# Micro_Rev1j.net
KiCad netlist of a schematic drawn in EAGLE
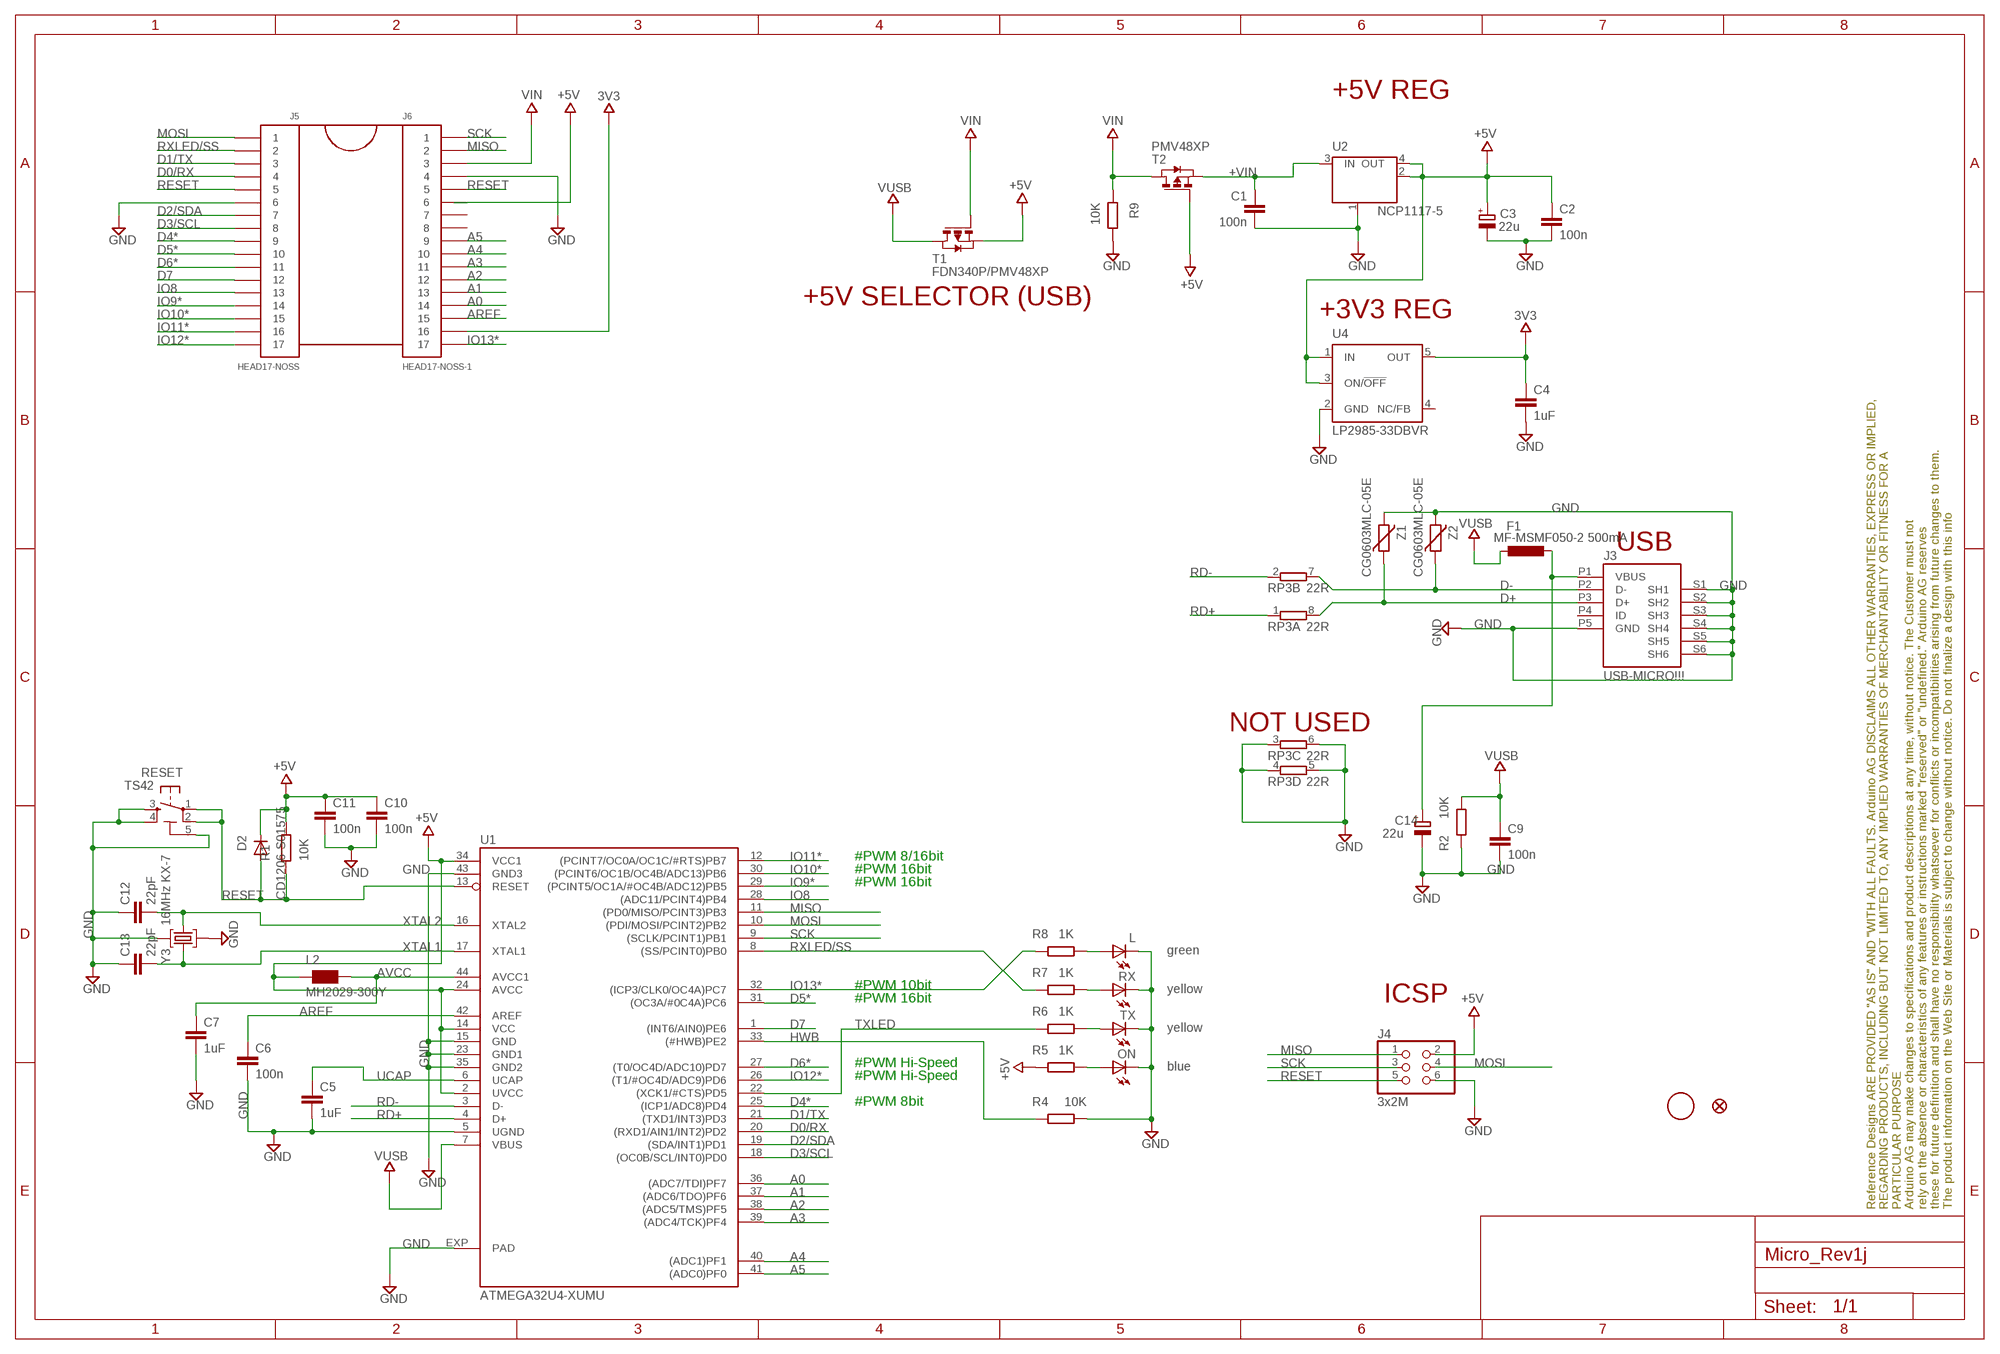
[diagram p0: schematic, sheet 1]

(export (version "E")
  (design (tool "Eeschema 10.0.6"))
  (components
    (comp (ref "C1")
      (value "100n")
      (footprint "eagle-import:C0402")
      (libsource (lib "eagle-import") (part "C-EUC0402"))
    )
    (comp (ref "C2")
      (value "100n")
      (footprint "eagle-import:C0402")
      (libsource (lib "eagle-import") (part "C-EUC0402"))
    )
    (comp (ref "C3")
      (value "22u")
      (footprint "eagle-import:SMC_B")
      (libsource (lib "eagle-import") (part "CPOL-EUSMCB"))
    )
    (comp (ref "C4")
      (value "1uF")
      (footprint "eagle-import:C0402")
      (libsource (lib "eagle-import") (part "C-EUC0402"))
    )
    (comp (ref "C5")
      (value "1uF")
      (footprint "eagle-import:C0402")
      (libsource (lib "eagle-import") (part "C-EUC0402"))
    )
    (comp (ref "C6")
      (value "100n")
      (footprint "eagle-import:C0402")
      (libsource (lib "eagle-import") (part "C-EUC0402"))
    )
    (comp (ref "C7")
      (value "1uF")
      (footprint "eagle-import:C0402")
      (libsource (lib "eagle-import") (part "C-EUC0402"))
    )
    (comp (ref "C9")
      (value "100n")
      (footprint "eagle-import:C0402")
      (libsource (lib "eagle-import") (part "C-EUC0402"))
    )
    (comp (ref "C10")
      (value "100n")
      (footprint "eagle-import:C0402")
      (libsource (lib "eagle-import") (part "C-EUC0402"))
    )
    (comp (ref "C11")
      (value "100n")
      (footprint "eagle-import:C0402")
      (libsource (lib "eagle-import") (part "C-EUC0402"))
    )
    (comp (ref "C12")
      (value "22pF")
      (footprint "eagle-import:C0402")
      (libsource (lib "eagle-import") (part "C-EUC0402"))
    )
    (comp (ref "C13")
      (value "22pF")
      (footprint "eagle-import:C0402")
      (libsource (lib "eagle-import") (part "C-EUC0402"))
    )
    (comp (ref "C14")
      (value "22u")
      (footprint "eagle-import:SMC_B")
      (libsource (lib "eagle-import") (part "CPOL-EUSMCB"))
    )
    (comp (ref "D2")
      (value "CD1206-S01575")
      (footprint "eagle-import:MINIMELF")
      (libsource (lib "eagle-import") (part "DIODE-MINIMELF"))
    )
    (comp (ref "F1")
      (value "MF-MSMF050-2 500mA")
      (footprint "eagle-import:L1812")
      (libsource (lib "eagle-import") (part "L-EUL1812"))
    )
    (comp (ref "FRAME1")
      (value "DNP")
      (footprint "eagle-import:FRAME")
      (libsource (lib "eagle-import") (part "A3-FRAME-STANDARD"))
    )
    (comp (ref "J3")
      (value "USB-MICRO!!!")
      (footprint "eagle-import:CON2_USB_MICRO_B_AT")
      (libsource (lib "eagle-import") (part "MYCON2_USB-MINI-B"))
    )
    (comp (ref "J4")
      (value "3x2M")
      (footprint "eagle-import:2X03")
      (libsource (lib "eagle-import") (part "PINHD-2X3"))
    )
    (comp (ref "J5")
      (value "HEAD17-NOSS")
      (footprint "eagle-import:HEAD17-NOSS")
      (libsource (lib "eagle-import") (part "HEAD17-NOSS"))
    )
    (comp (ref "J6")
      (value "HEAD17-NOSS-1")
      (footprint "eagle-import:HEAD17-NOSS-1")
      (libsource (lib "eagle-import") (part "HEAD17-NOSS-1"))
    )
    (comp (ref "L")
      (value "green")
      (footprint "eagle-import:CHIPLED_0805")
      (libsource (lib "eagle-import") (part "LEDCHIPLED_0805"))
    )
    (comp (ref "L2")
      (value "MH2029-300Y")
      (footprint "eagle-import:0805")
      (libsource (lib "eagle-import") (part "WE-CBF_0805"))
    )
    (comp (ref "ON")
      (value "blue")
      (footprint "eagle-import:CHIPLED_0805")
      (libsource (lib "eagle-import") (part "LEDCHIPLED_0805"))
    )
    (comp (ref "R1")
      (value "10K")
      (footprint "eagle-import:R0402")
      (libsource (lib "eagle-import") (part "R-EU_R0402"))
    )
    (comp (ref "R2")
      (value "10K")
      (footprint "eagle-import:R0402")
      (libsource (lib "eagle-import") (part "R-EU_R0402"))
    )
    (comp (ref "R4")
      (value "10K")
      (footprint "eagle-import:R0402")
      (libsource (lib "eagle-import") (part "R-EU_R0402"))
    )
    (comp (ref "R5")
      (value "1K")
      (footprint "eagle-import:R0402")
      (libsource (lib "eagle-import") (part "R-EU_R0402"))
    )
    (comp (ref "R6")
      (value "1K")
      (footprint "eagle-import:R0402")
      (libsource (lib "eagle-import") (part "R-EU_R0402"))
    )
    (comp (ref "R7")
      (value "1K")
      (footprint "eagle-import:R0402")
      (libsource (lib "eagle-import") (part "R-EU_R0402"))
    )
    (comp (ref "R8")
      (value "1K")
      (footprint "eagle-import:R0402")
      (libsource (lib "eagle-import") (part "R-EU_R0402"))
    )
    (comp (ref "R9")
      (value "10K")
      (footprint "eagle-import:R0402")
      (libsource (lib "eagle-import") (part "R-EU_R0402"))
    )
    (comp (ref "RESET")
      (value "TS42")
      (footprint "eagle-import:TS42")
      (libsource (lib "eagle-import") (part "TS42"))
    )
    (comp (ref "RP3")
      (value "22R")
      (footprint "eagle-import:CAY16")
      (libsource (lib "eagle-import") (part "4R-NCAY16"))
    )
    (comp (ref "RX")
      (value "yellow")
      (footprint "eagle-import:CHIPLED_0805")
      (libsource (lib "eagle-import") (part "LEDCHIPLED_0805"))
    )
    (comp (ref "T1")
      (value "FDN340P/PMV48XP")
      (footprint "eagle-import:SOT-23")
      (libsource (lib "eagle-import") (part "PMOSSOT23"))
    )
    (comp (ref "T2")
      (value "PMV48XP")
      (footprint "eagle-import:SOT-23")
      (libsource (lib "eagle-import") (part "PMOSSOT23"))
    )
    (comp (ref "TX")
      (value "yellow")
      (footprint "eagle-import:CHIPLED_0805")
      (libsource (lib "eagle-import") (part "LEDCHIPLED_0805"))
    )
    (comp (ref "U$37")
      (value "FIDUCIALMOUNT")
      (footprint "eagle-import:FIDUCIA-MOUNT")
      (libsource (lib "eagle-import") (part "FIDUCIALMOUNT"))
    )
    (comp (ref "U$53")
      (value "FIDUCIAL1X2")
      (footprint "eagle-import:FIDUCIAL-1X2")
      (libsource (lib "eagle-import") (part "FIDUCIAL1X2"))
    )
    (comp (ref "U1")
      (value "ATMEGA32U4-XUMU")
      (footprint "eagle-import:QFN44ML7X7")
      (libsource (lib "eagle-import") (part "ATMEGA32U4-XUMU"))
    )
    (comp (ref "U2")
      (value "NCP1117-5")
      (footprint "eagle-import:SOT223")
      (libsource (lib "eagle-import") (part "LINEAR_MC33269ST"))
    )
    (comp (ref "U4")
      (value "LP2985-33DBVR")
      (footprint "eagle-import:SOT23-DBV")
      (libsource (lib "eagle-import") (part "LP2985-XXDBVR33"))
    )
    (comp (ref "Y3")
      (value "16MHz KX-7")
      (footprint "eagle-import:CRYSTAL-3.2-2.5")
      (libsource (lib "eagle-import") (part "CRYSTAL-3.2-2.5"))
    )
    (comp (ref "Z1")
      (value "CG0603MLC-05E")
      (footprint "eagle-import:CT_CN0603")
      (libsource (lib "eagle-import") (part "VARISTORCN0603"))
    )
    (comp (ref "Z2")
      (value "CG0603MLC-05E")
      (footprint "eagle-import:CT_CN0603")
      (libsource (lib "eagle-import") (part "VARISTORCN0603"))
    )
  )
  (nets
    (net (code "1") (name "+5V") (class "Default")
      (node (ref "C10") (pin "1") (pinfunction "1_1") (pintype "passive"))
      (node (ref "C11") (pin "1") (pinfunction "1_1") (pintype "passive"))
      (node (ref "C2") (pin "1") (pinfunction "1_1") (pintype "passive"))
      (node (ref "C3") (pin "+") (pinfunction "+_+") (pintype "passive"))
      (node (ref "D2") (pin "C") (pinfunction "C_C") (pintype "passive"))
      (node (ref "J4") (pin "2") (pinfunction "2_2") (pintype "passive"))
      (node (ref "J6") (pin "6") (pinfunction "6_6") (pintype "passive"))
      (node (ref "L2") (pin "1") (pinfunction "1_1") (pintype "passive"))
      (node (ref "R1") (pin "1") (pinfunction "1_1") (pintype "passive"))
      (node (ref "R5") (pin "1") (pinfunction "1_1") (pintype "passive"))
      (node (ref "T1") (pin "2") (pinfunction "S_2") (pintype "passive"))
      (node (ref "T2") (pin "3") (pinfunction "G_3") (pintype "passive"))
      (node (ref "U1") (pin "14") (pinfunction "VCC_14") (pintype "power_in"))
      (node (ref "U1") (pin "2") (pinfunction "UVCC_2") (pintype "power_in"))
      (node (ref "U1") (pin "24") (pinfunction "AVCC_24") (pintype "power_in"))
      (node (ref "U1") (pin "34") (pinfunction "VCC1_34") (pintype "power_in"))
      (node (ref "U2") (pin "2") (pinfunction "OUT_2") (pintype "passive"))
      (node (ref "U2") (pin "4") (pinfunction "OUT_4") (pintype "passive"))
      (node (ref "U4") (pin "1") (pinfunction "IN_1") (pintype "input"))
      (node (ref "U4") (pin "3") (pinfunction "ON/~{OFF}_3") (pintype "input"))
    )
    (net (code "2") (name "/+VIN") (class "Default")
      (node (ref "C1") (pin "1") (pinfunction "1_1") (pintype "passive"))
      (node (ref "T2") (pin "2") (pinfunction "S_2") (pintype "passive"))
      (node (ref "U2") (pin "3") (pinfunction "IN_3") (pintype "input"))
    )
    (net (code "3") (name "/A0") (class "Default")
      (node (ref "J6") (pin "14") (pinfunction "14_14") (pintype "passive"))
      (node (ref "U1") (pin "36") (pinfunction "(ADC7/TDI)PF7_36") (pintype "bidirectional"))
    )
    (net (code "4") (name "/A1") (class "Default")
      (node (ref "J6") (pin "13") (pinfunction "13_13") (pintype "passive"))
      (node (ref "U1") (pin "37") (pinfunction "(ADC6/TDO)PF6_37") (pintype "bidirectional"))
    )
    (net (code "5") (name "/A2") (class "Default")
      (node (ref "J6") (pin "12") (pinfunction "12_12") (pintype "passive"))
      (node (ref "U1") (pin "38") (pinfunction "(ADC5/TMS)PF5_38") (pintype "bidirectional"))
    )
    (net (code "6") (name "/A3") (class "Default")
      (node (ref "J6") (pin "11") (pinfunction "11_11") (pintype "passive"))
      (node (ref "U1") (pin "39") (pinfunction "(ADC4/TCK)PF4_39") (pintype "bidirectional"))
    )
    (net (code "7") (name "/A4") (class "Default")
      (node (ref "J6") (pin "10") (pinfunction "10_10") (pintype "passive"))
      (node (ref "U1") (pin "40") (pinfunction "(ADC1)PF1_40") (pintype "bidirectional"))
    )
    (net (code "8") (name "/A5") (class "Default")
      (node (ref "J6") (pin "9") (pinfunction "9_9") (pintype "passive"))
      (node (ref "U1") (pin "41") (pinfunction "(ADC0)PF0_41") (pintype "bidirectional"))
    )
    (net (code "9") (name "/AREF") (class "Default")
      (node (ref "C6") (pin "1") (pinfunction "1_1") (pintype "passive"))
      (node (ref "J6") (pin "15") (pinfunction "15_15") (pintype "passive"))
      (node (ref "U1") (pin "42") (pinfunction "AREF_42") (pintype "power_in"))
    )
    (net (code "10") (name "/AVCC") (class "Default")
      (node (ref "C7") (pin "1") (pinfunction "1_1") (pintype "passive"))
      (node (ref "L2") (pin "2") (pinfunction "2_2") (pintype "passive"))
      (node (ref "U1") (pin "44") (pinfunction "AVCC1_44") (pintype "power_in"))
    )
    (net (code "11") (name "/D+") (class "Default")
      (node (ref "J3") (pin "P3") (pinfunction "D+_P3") (pintype "bidirectional"))
      (node (ref "RP3") (pin "8") (pinfunction "2_8") (pintype "passive"))
      (node (ref "Z1") (pin "1") (pinfunction "1_1") (pintype "passive"))
    )
    (net (code "12") (name "/D-") (class "Default")
      (node (ref "J3") (pin "P2") (pinfunction "D-_P2") (pintype "bidirectional"))
      (node (ref "RP3") (pin "7") (pinfunction "2_7") (pintype "passive"))
      (node (ref "Z2") (pin "1") (pinfunction "1_1") (pintype "passive"))
    )
    (net (code "13") (name "/D0{slash}RX") (class "Default")
      (node (ref "J5") (pin "4") (pinfunction "4_4") (pintype "passive"))
      (node (ref "U1") (pin "20") (pinfunction "(RXD1/AIN1/INT2)PD2_20") (pintype "bidirectional"))
    )
    (net (code "14") (name "/D1{slash}TX") (class "Default")
      (node (ref "J5") (pin "3") (pinfunction "3_3") (pintype "passive"))
      (node (ref "U1") (pin "21") (pinfunction "(TXD1/INT3)PD3_21") (pintype "bidirectional"))
    )
    (net (code "15") (name "/D2{slash}SDA") (class "Default")
      (node (ref "J5") (pin "7") (pinfunction "7_7") (pintype "passive"))
      (node (ref "U1") (pin "19") (pinfunction "(SDA/INT1)PD1_19") (pintype "bidirectional"))
    )
    (net (code "16") (name "/D3{slash}SCL") (class "Default")
      (node (ref "J5") (pin "8") (pinfunction "8_8") (pintype "passive"))
      (node (ref "U1") (pin "18") (pinfunction "(OC0B/SCL/INT0)PD0_18") (pintype "bidirectional"))
    )
    (net (code "17") (name "/D4*") (class "Default")
      (node (ref "J5") (pin "9") (pinfunction "9_9") (pintype "passive"))
      (node (ref "U1") (pin "25") (pinfunction "(ICP1/ADC8)PD4_25") (pintype "bidirectional"))
    )
    (net (code "18") (name "/D5*") (class "Default")
      (node (ref "J5") (pin "10") (pinfunction "10_10") (pintype "passive"))
      (node (ref "U1") (pin "31") (pinfunction "(OC3A/#0C4A)PC6_31") (pintype "bidirectional"))
    )
    (net (code "19") (name "/D6*") (class "Default")
      (node (ref "J5") (pin "11") (pinfunction "11_11") (pintype "passive"))
      (node (ref "U1") (pin "27") (pinfunction "(T0/OC4D/ADC10)PD7_27") (pintype "bidirectional"))
    )
    (net (code "20") (name "/D7") (class "Default")
      (node (ref "J5") (pin "12") (pinfunction "12_12") (pintype "passive"))
      (node (ref "U1") (pin "1") (pinfunction "(INT6/AIN0)PE6_1") (pintype "bidirectional"))
    )
    (net (code "21") (name "/HWB") (class "Default")
      (node (ref "R4") (pin "1") (pinfunction "1_1") (pintype "passive"))
      (node (ref "U1") (pin "33") (pinfunction "(#HWB)PE2_33") (pintype "bidirectional"))
    )
    (net (code "22") (name "/IO8") (class "Default")
      (node (ref "J5") (pin "13") (pinfunction "13_13") (pintype "passive"))
      (node (ref "U1") (pin "28") (pinfunction "(ADC11/PCINT4)PB4_28") (pintype "bidirectional"))
    )
    (net (code "23") (name "/IO9*") (class "Default")
      (node (ref "J5") (pin "14") (pinfunction "14_14") (pintype "passive"))
      (node (ref "U1") (pin "29") (pinfunction "(PCINT5/OC1A/#OC4B/ADC12)PB5_29") (pintype "bidirectional"))
    )
    (net (code "24") (name "/IO10*") (class "Default")
      (node (ref "J5") (pin "15") (pinfunction "15_15") (pintype "passive"))
      (node (ref "U1") (pin "30") (pinfunction "(PCINT6/OC1B/OC4B/ADC13)PB6_30") (pintype "bidirectional"))
    )
    (net (code "25") (name "/IO11*") (class "Default")
      (node (ref "J5") (pin "16") (pinfunction "16_16") (pintype "passive"))
      (node (ref "U1") (pin "12") (pinfunction "(PCINT7/OC0A/OC1C/#RTS)PB7_12") (pintype "bidirectional"))
    )
    (net (code "26") (name "/IO12*") (class "Default")
      (node (ref "J5") (pin "17") (pinfunction "17_17") (pintype "passive"))
      (node (ref "U1") (pin "26") (pinfunction "(T1/#OC4D/ADC9)PD6_26") (pintype "bidirectional"))
    )
    (net (code "27") (name "/IO13*") (class "Default")
      (node (ref "J6") (pin "17") (pinfunction "17_17") (pintype "passive"))
      (node (ref "R8") (pin "1") (pinfunction "1_1") (pintype "passive"))
      (node (ref "U1") (pin "32") (pinfunction "(ICP3/CLK0/OC4A)PC7_32") (pintype "bidirectional"))
    )
    (net (code "28") (name "/MISO") (class "Default")
      (node (ref "J4") (pin "1") (pinfunction "1_1") (pintype "passive"))
      (node (ref "J6") (pin "2") (pinfunction "2_2") (pintype "passive"))
      (node (ref "U1") (pin "11") (pinfunction "(PD0/MISO/PCINT3)PB3_11") (pintype "bidirectional"))
    )
    (net (code "29") (name "/MOSI") (class "Default")
      (node (ref "J4") (pin "4") (pinfunction "4_4") (pintype "passive"))
      (node (ref "J5") (pin "1") (pinfunction "1_1") (pintype "passive"))
      (node (ref "U1") (pin "10") (pinfunction "(PDI/MOSI/PCINT2)PB2_10") (pintype "bidirectional"))
    )
    (net (code "30") (name "/RD+") (class "Default")
      (node (ref "RP3") (pin "1") (pinfunction "1_1") (pintype "passive"))
      (node (ref "U1") (pin "4") (pinfunction "D+_4") (pintype "bidirectional"))
    )
    (net (code "31") (name "/RD-") (class "Default")
      (node (ref "RP3") (pin "2") (pinfunction "1_2") (pintype "passive"))
      (node (ref "U1") (pin "3") (pinfunction "D-_3") (pintype "bidirectional"))
    )
    (net (code "32") (name "/RESET") (class "Default")
      (node (ref "D2") (pin "A") (pinfunction "A_A") (pintype "passive"))
      (node (ref "J4") (pin "5") (pinfunction "5_5") (pintype "passive"))
      (node (ref "J5") (pin "5") (pinfunction "5_5") (pintype "passive"))
      (node (ref "J6") (pin "5") (pinfunction "5_5") (pintype "passive"))
      (node (ref "R1") (pin "2") (pinfunction "2_2") (pintype "passive"))
      (node (ref "RESET") (pin "1") (pinfunction "1_1") (pintype "passive"))
      (node (ref "RESET") (pin "2") (pinfunction "2_2") (pintype "passive"))
      (node (ref "U1") (pin "13") (pinfunction "RESET_13") (pintype "input"))
    )
    (net (code "33") (name "/RXLED{slash}SS") (class "Default")
      (node (ref "J5") (pin "2") (pinfunction "2_2") (pintype "passive"))
      (node (ref "R7") (pin "1") (pinfunction "1_1") (pintype "passive"))
      (node (ref "U1") (pin "8") (pinfunction "(SS/PCINT0)PB0_8") (pintype "bidirectional"))
    )
    (net (code "34") (name "/SCK") (class "Default")
      (node (ref "J4") (pin "3") (pinfunction "3_3") (pintype "passive"))
      (node (ref "J6") (pin "1") (pinfunction "1_1") (pintype "passive"))
      (node (ref "U1") (pin "9") (pinfunction "(SCLK/PCINT1)PB1_9") (pintype "bidirectional"))
    )
    (net (code "35") (name "/TXLED") (class "Default")
      (node (ref "R6") (pin "1") (pinfunction "1_1") (pintype "passive"))
      (node (ref "U1") (pin "22") (pinfunction "(XCK1/#CTS)PD5_22") (pintype "bidirectional"))
    )
    (net (code "36") (name "/UCAP") (class "Default")
      (node (ref "C5") (pin "1") (pinfunction "1_1") (pintype "passive"))
      (node (ref "U1") (pin "6") (pinfunction "UCAP_6") (pintype "passive"))
    )
    (net (code "37") (name "/XTAL1") (class "Default")
      (node (ref "C13") (pin "2") (pinfunction "2_2") (pintype "passive"))
      (node (ref "U1") (pin "17") (pinfunction "XTAL1_17") (pintype "bidirectional"))
      (node (ref "Y3") (pin "3") (pinfunction "C2_3") (pintype "passive"))
    )
    (net (code "38") (name "/XTAL2") (class "Default")
      (node (ref "C12") (pin "2") (pinfunction "2_2") (pintype "passive"))
      (node (ref "U1") (pin "16") (pinfunction "XTAL2_16") (pintype "bidirectional"))
      (node (ref "Y3") (pin "1") (pinfunction "C1_1") (pintype "passive"))
    )
    (net (code "39") (name "3V3") (class "Default")
      (node (ref "C4") (pin "1") (pinfunction "1_1") (pintype "passive"))
      (node (ref "J6") (pin "16") (pinfunction "16_16") (pintype "passive"))
      (node (ref "U4") (pin "5") (pinfunction "OUT_5") (pintype "passive"))
    )
    (net (code "40") (name "GND") (class "Default")
      (node (ref "C1") (pin "2") (pinfunction "2_2") (pintype "passive"))
      (node (ref "C10") (pin "2") (pinfunction "2_2") (pintype "passive"))
      (node (ref "C11") (pin "2") (pinfunction "2_2") (pintype "passive"))
      (node (ref "C12") (pin "1") (pinfunction "1_1") (pintype "passive"))
      (node (ref "C13") (pin "1") (pinfunction "1_1") (pintype "passive"))
      (node (ref "C14") (pin "-") (pinfunction "-_-") (pintype "passive"))
      (node (ref "C2") (pin "2") (pinfunction "2_2") (pintype "passive"))
      (node (ref "C3") (pin "-") (pinfunction "-_-") (pintype "passive"))
      (node (ref "C4") (pin "2") (pinfunction "2_2") (pintype "passive"))
      (node (ref "C5") (pin "2") (pinfunction "2_2") (pintype "passive"))
      (node (ref "C6") (pin "2") (pinfunction "2_2") (pintype "passive"))
      (node (ref "C7") (pin "2") (pinfunction "2_2") (pintype "passive"))
      (node (ref "C9") (pin "2") (pinfunction "2_2") (pintype "passive"))
      (node (ref "J3") (pin "P5") (pinfunction "GND_P5") (pintype "passive"))
      (node (ref "J3") (pin "S1") (pinfunction "SH1_S1") (pintype "passive"))
      (node (ref "J3") (pin "S2") (pinfunction "SH2_S2") (pintype "passive"))
      (node (ref "J3") (pin "S3") (pinfunction "SH3_S3") (pintype "passive"))
      (node (ref "J3") (pin "S4") (pinfunction "SH4_S4") (pintype "passive"))
      (node (ref "J3") (pin "S5") (pinfunction "SH5_S5") (pintype "passive"))
      (node (ref "J3") (pin "S6") (pinfunction "SH6_S6") (pintype "passive"))
      (node (ref "J4") (pin "6") (pinfunction "6_6") (pintype "passive"))
      (node (ref "J5") (pin "6") (pinfunction "6_6") (pintype "passive"))
      (node (ref "J6") (pin "4") (pinfunction "4_4") (pintype "passive"))
      (node (ref "L") (pin "C") (pinfunction "C_C") (pintype "passive"))
      (node (ref "ON") (pin "C") (pinfunction "C_C") (pintype "passive"))
      (node (ref "R2") (pin "1") (pinfunction "1_1") (pintype "passive"))
      (node (ref "R4") (pin "2") (pinfunction "2_2") (pintype "passive"))
      (node (ref "R9") (pin "1") (pinfunction "1_1") (pintype "passive"))
      (node (ref "RESET") (pin "3") (pinfunction "3_3") (pintype "passive"))
      (node (ref "RESET") (pin "4") (pinfunction "4_4") (pintype "passive"))
      (node (ref "RESET") (pin "5") (pinfunction "5-GND_5") (pintype "power_in"))
      (node (ref "RP3") (pin "3") (pinfunction "1_3") (pintype "passive"))
      (node (ref "RP3") (pin "4") (pinfunction "1_4") (pintype "passive"))
      (node (ref "RP3") (pin "5") (pinfunction "2_5") (pintype "passive"))
      (node (ref "RP3") (pin "6") (pinfunction "2_6") (pintype "passive"))
      (node (ref "RX") (pin "C") (pinfunction "C_C") (pintype "passive"))
      (node (ref "TX") (pin "C") (pinfunction "C_C") (pintype "passive"))
      (node (ref "U1") (pin "15") (pinfunction "GND_15") (pintype "power_in"))
      (node (ref "U1") (pin "23") (pinfunction "GND1_23") (pintype "power_in"))
      (node (ref "U1") (pin "35") (pinfunction "GND2_35") (pintype "power_in"))
      (node (ref "U1") (pin "43") (pinfunction "GND3_43") (pintype "power_in"))
      (node (ref "U1") (pin "5") (pinfunction "UGND_5") (pintype "power_in"))
      (node (ref "U1") (pin "EXP") (pinfunction "PAD_EXP") (pintype "power_in"))
      (node (ref "U2") (pin "1") (pinfunction "GND/ADJ_1") (pintype "input"))
      (node (ref "U4") (pin "2") (pinfunction "GND_2") (pintype "power_in"))
      (node (ref "Y3") (pin "2") (pinfunction "GND_2") (pintype "passive"))
      (node (ref "Y3") (pin "4") (pinfunction "GND_4") (pintype "passive"))
      (node (ref "Z1") (pin "2") (pinfunction "2_2") (pintype "passive"))
      (node (ref "Z2") (pin "2") (pinfunction "2_2") (pintype "passive"))
    )
    (net (code "41") (name "Net-(J3-VBUS)") (class "Default")
      (node (ref "C14") (pin "+") (pinfunction "+_+") (pintype "passive"))
      (node (ref "F1") (pin "1") (pinfunction "1_1") (pintype "passive"))
      (node (ref "J3") (pin "P1") (pinfunction "VBUS_P1") (pintype "power_in"))
    )
    (net (code "42") (name "Net-(L-PadA)") (class "Default")
      (node (ref "L") (pin "A") (pinfunction "A_A") (pintype "passive"))
      (node (ref "R8") (pin "2") (pinfunction "2_2") (pintype "passive"))
    )
    (net (code "43") (name "Net-(ON-PadA)") (class "Default")
      (node (ref "ON") (pin "A") (pinfunction "A_A") (pintype "passive"))
      (node (ref "R5") (pin "2") (pinfunction "2_2") (pintype "passive"))
    )
    (net (code "44") (name "Net-(R6-Pad2)") (class "Default")
      (node (ref "R6") (pin "2") (pinfunction "2_2") (pintype "passive"))
      (node (ref "TX") (pin "A") (pinfunction "A_A") (pintype "passive"))
    )
    (net (code "45") (name "Net-(R7-Pad2)") (class "Default")
      (node (ref "R7") (pin "2") (pinfunction "2_2") (pintype "passive"))
      (node (ref "RX") (pin "A") (pinfunction "A_A") (pintype "passive"))
    )
    (net (code "46") (name "VIN") (class "Default")
      (node (ref "J6") (pin "3") (pinfunction "3_3") (pintype "passive"))
      (node (ref "R9") (pin "2") (pinfunction "2_2") (pintype "passive"))
      (node (ref "T1") (pin "3") (pinfunction "G_3") (pintype "passive"))
      (node (ref "T2") (pin "1") (pinfunction "D_1") (pintype "passive"))
    )
    (net (code "47") (name "VUSB") (class "Default")
      (node (ref "C9") (pin "1") (pinfunction "1_1") (pintype "passive"))
      (node (ref "F1") (pin "2") (pinfunction "2_2") (pintype "passive"))
      (node (ref "R2") (pin "2") (pinfunction "2_2") (pintype "passive"))
      (node (ref "T1") (pin "1") (pinfunction "D_1") (pintype "passive"))
      (node (ref "U1") (pin "7") (pinfunction "VBUS_7") (pintype "input"))
    )
    (net (code "48") (name "unconnected-(J3-ID-PadP4)") (class "Default")
      (node (ref "J3") (pin "P4") (pinfunction "ID_P4") (pintype "bidirectional"))
    )
    (net (code "49") (name "unconnected-(J6-Pad7)") (class "Default")
      (node (ref "J6") (pin "7") (pinfunction "7_7") (pintype "passive"))
    )
    (net (code "50") (name "unconnected-(J6-Pad8)") (class "Default")
      (node (ref "J6") (pin "8") (pinfunction "8_8") (pintype "passive"))
    )
    (net (code "51") (name "unconnected-(U4-NC{slash}FB-Pad4)") (class "Default")
      (node (ref "U4") (pin "4") (pinfunction "NC/FB_4") (pintype "passive"))
    )
  )
)
